# caja_universal.net
KiCad netlist of a schematic drawn in EAGLE
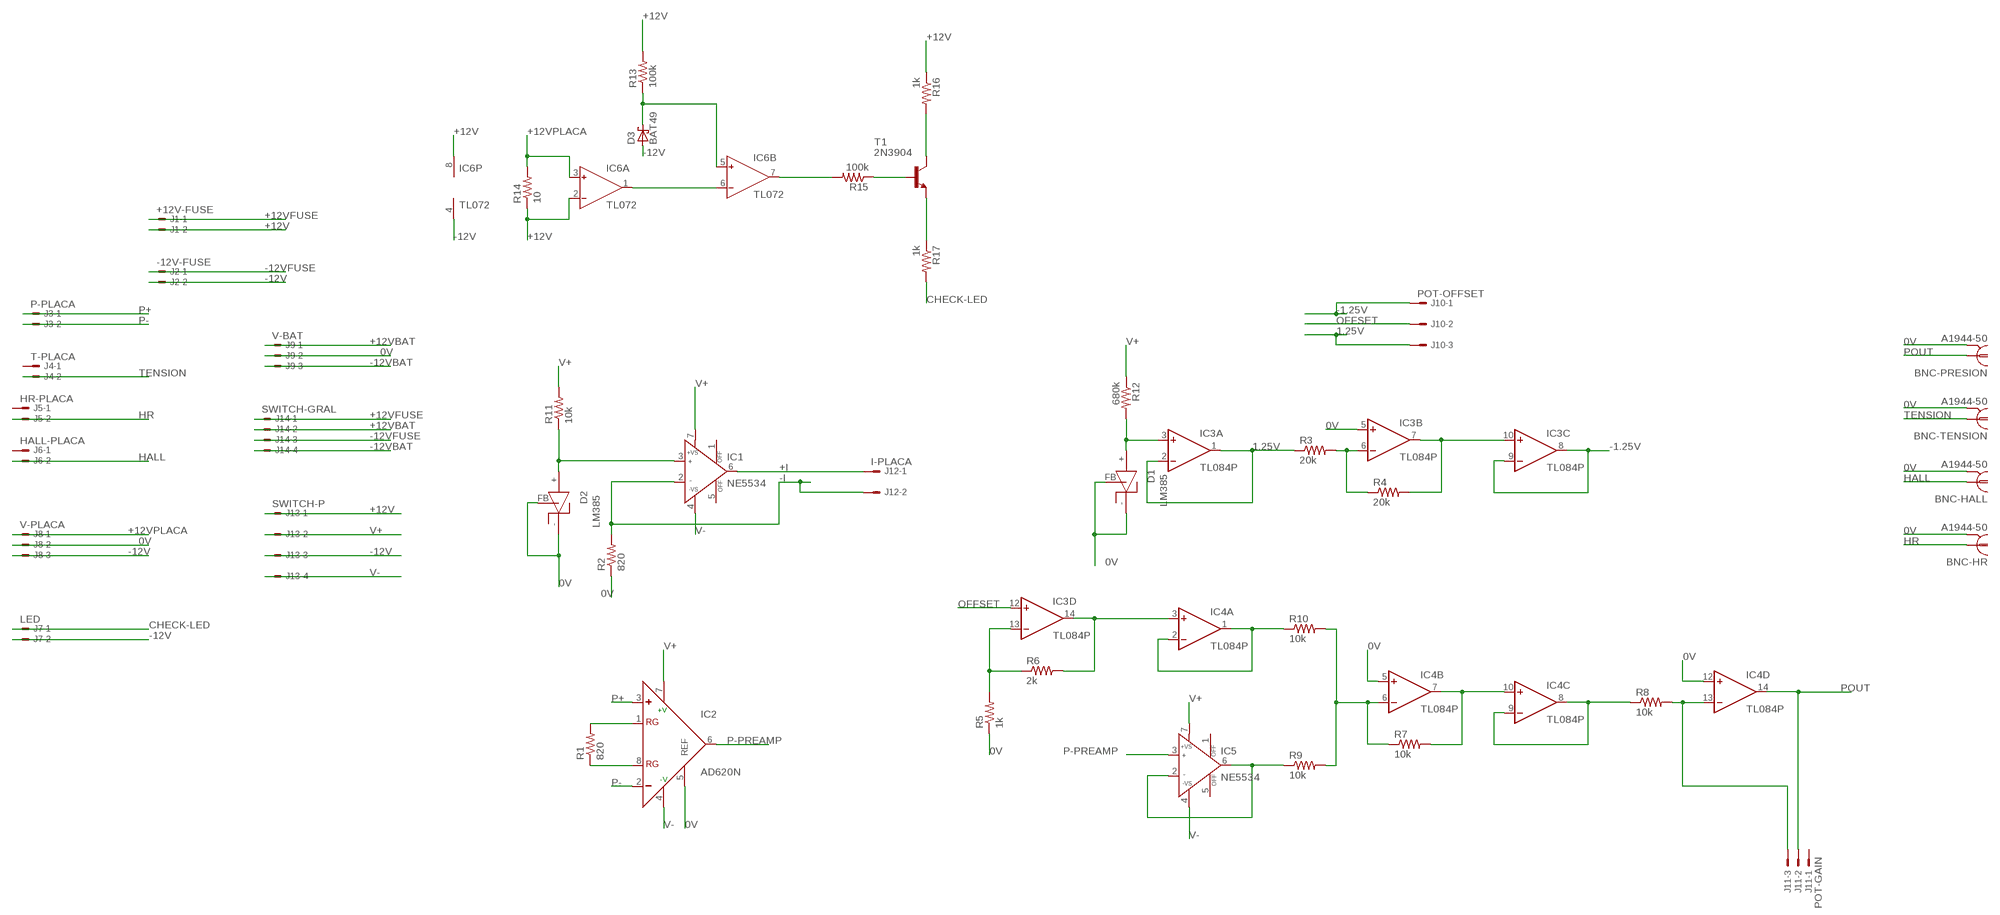
[diagram p0: schematic, sheet 1]

(export (version "E")
  (design (tool "Eeschema 10.0.6"))
  (components
    (comp (ref "BNC-HALL")
      (value "A1944-50")
      (footprint "eagle-import:A1944")
      (libsource (lib "eagle-import") (part "A1944-50"))
    )
    (comp (ref "BNC-HR")
      (value "A1944-50")
      (footprint "eagle-import:A1944")
      (libsource (lib "eagle-import") (part "A1944-50"))
    )
    (comp (ref "BNC-PRESION")
      (value "A1944-50")
      (footprint "eagle-import:A1944")
      (libsource (lib "eagle-import") (part "A1944-50"))
    )
    (comp (ref "BNC-TENSION")
      (value "A1944-50")
      (footprint "eagle-import:A1944")
      (libsource (lib "eagle-import") (part "A1944-50"))
    )
    (comp (ref "D1")
      (value "LM385")
      (footprint "eagle-import:TO-92")
      (libsource (lib "eagle-import") (part "LM385"))
    )
    (comp (ref "D2")
      (value "LM385")
      (footprint "eagle-import:TO-92")
      (libsource (lib "eagle-import") (part "LM385"))
    )
    (comp (ref "D3")
      (value "BAT49")
      (footprint "eagle-import:DO41-10")
      (libsource (lib "eagle-import") (part "BAT49"))
    )
    (comp (ref "IC1")
      (value "NE5534")
      (footprint "eagle-import:DIL08")
      (fields (field (name "MPN") "AD711BQ"))
      (libsource (lib "eagle-import") (part "AD711N"))
    )
    (comp (ref "IC2")
      (value "AD620N")
      (footprint "eagle-import:DIL08")
      (fields (field (name "MF") "ALTERA CORPORATION") (field (name "MPN") "AD620AN"))
      (libsource (lib "eagle-import") (part "AD620N"))
    )
    (comp (ref "IC3")
      (value "TL084P")
      (footprint "eagle-import:DIL14")
      (libsource (lib "eagle-import") (part "TL084P"))
    )
    (comp (ref "IC4")
      (value "TL084P")
      (footprint "eagle-import:DIL14")
      (libsource (lib "eagle-import") (part "TL084P"))
    )
    (comp (ref "IC5")
      (value "NE5534")
      (footprint "eagle-import:DIL08")
      (fields (field (name "MPN") "AD711BQ"))
      (libsource (lib "eagle-import") (part "AD711N"))
    )
    (comp (ref "IC6")
      (value "TL072")
      (footprint "eagle-import:DIL08")
      (fields (field (name "MF") "ALTERA CORPORATION") (field (name "MPN") "AD826ANZ"))
      (libsource (lib "eagle-import") (part "AD826N"))
    )
    (comp (ref "J1")
      (value "+12V-FUSE")
      (footprint "eagle-import:6410-02")
      (libsource (lib "eagle-import") (part "22-?-0227-2021"))
    )
    (comp (ref "J2")
      (value "-12V-FUSE")
      (footprint "eagle-import:6410-02")
      (libsource (lib "eagle-import") (part "22-?-0227-2021"))
    )
    (comp (ref "J3")
      (value "P-PLACA")
      (footprint "eagle-import:6410-02")
      (libsource (lib "eagle-import") (part "22-?-0227-2021"))
    )
    (comp (ref "J4")
      (value "T-PLACA")
      (footprint "eagle-import:6410-02")
      (libsource (lib "eagle-import") (part "22-?-0227-2021"))
    )
    (comp (ref "J5")
      (value "HR-PLACA")
      (footprint "eagle-import:6410-02")
      (libsource (lib "eagle-import") (part "22-?-0227-2021"))
    )
    (comp (ref "J6")
      (value "HALL-PLACA")
      (footprint "eagle-import:6410-02")
      (libsource (lib "eagle-import") (part "22-?-0227-2021"))
    )
    (comp (ref "J7")
      (value "LED")
      (footprint "eagle-import:6410-02")
      (libsource (lib "eagle-import") (part "22-?-0227-2021"))
    )
    (comp (ref "J8")
      (value "V-PLACA")
      (footprint "eagle-import:6410-03")
      (libsource (lib "eagle-import") (part "22-?-0327-2031"))
    )
    (comp (ref "J9")
      (value "V-BAT")
      (footprint "eagle-import:6410-03")
      (libsource (lib "eagle-import") (part "22-?-0327-2031"))
    )
    (comp (ref "J10")
      (value "POT-OFFSET")
      (footprint "eagle-import:6410-03")
      (libsource (lib "eagle-import") (part "22-?-0327-2031"))
    )
    (comp (ref "J11")
      (value "POT-GAIN")
      (footprint "eagle-import:6410-03")
      (libsource (lib "eagle-import") (part "22-?-0327-2031"))
    )
    (comp (ref "J12")
      (value "I-PLACA")
      (footprint "eagle-import:6410-02")
      (libsource (lib "eagle-import") (part "22-?-0227-2021"))
    )
    (comp (ref "J13")
      (value "SWITCH-P")
      (footprint "eagle-import:6410-04")
      (libsource (lib "eagle-import") (part "22-?-0427-2041"))
    )
    (comp (ref "J14")
      (value "SWITCH-GRAL")
      (footprint "eagle-import:6410-04")
      (libsource (lib "eagle-import") (part "22-?-0427-2041"))
    )
    (comp (ref "R1")
      (value "820")
      (footprint "eagle-import:0204_7")
      (libsource (lib "eagle-import") (part "R-US_0204/7"))
    )
    (comp (ref "R2")
      (value "820")
      (footprint "eagle-import:0204_7")
      (libsource (lib "eagle-import") (part "R-US_0204/7"))
    )
    (comp (ref "R3")
      (value "20k")
      (footprint "eagle-import:0204_7")
      (libsource (lib "eagle-import") (part "R-US_0204/7"))
    )
    (comp (ref "R4")
      (value "20k")
      (footprint "eagle-import:0204_7")
      (libsource (lib "eagle-import") (part "R-US_0204/7"))
    )
    (comp (ref "R5")
      (value "1k")
      (footprint "eagle-import:0204_7")
      (libsource (lib "eagle-import") (part "R-US_0204/7"))
    )
    (comp (ref "R6")
      (value "2k")
      (footprint "eagle-import:0204_7")
      (libsource (lib "eagle-import") (part "R-US_0204/7"))
    )
    (comp (ref "R7")
      (value "10k")
      (footprint "eagle-import:0204_7")
      (libsource (lib "eagle-import") (part "R-US_0204/7"))
    )
    (comp (ref "R8")
      (value "10k")
      (footprint "eagle-import:0204_7")
      (libsource (lib "eagle-import") (part "R-US_0204/7"))
    )
    (comp (ref "R9")
      (value "10k")
      (footprint "eagle-import:0204_7")
      (libsource (lib "eagle-import") (part "R-US_0204/7"))
    )
    (comp (ref "R10")
      (value "10k")
      (footprint "eagle-import:0204_7")
      (libsource (lib "eagle-import") (part "R-US_0204/7"))
    )
    (comp (ref "R11")
      (value "10k")
      (footprint "eagle-import:0204_7")
      (libsource (lib "eagle-import") (part "R-US_0204/7"))
    )
    (comp (ref "R12")
      (value "680k")
      (footprint "eagle-import:0204_7")
      (libsource (lib "eagle-import") (part "R-US_0204/7"))
    )
    (comp (ref "R13")
      (value "100k")
      (footprint "eagle-import:0204_7")
      (libsource (lib "eagle-import") (part "R-US_0204/7"))
    )
    (comp (ref "R14")
      (value "10")
      (footprint "eagle-import:0204_7")
      (libsource (lib "eagle-import") (part "R-US_0204/7"))
    )
    (comp (ref "R15")
      (value "100k")
      (footprint "eagle-import:0204_7")
      (libsource (lib "eagle-import") (part "R-US_0204/7"))
    )
    (comp (ref "R16")
      (value "1k")
      (footprint "eagle-import:0204_7")
      (libsource (lib "eagle-import") (part "R-US_0204/7"))
    )
    (comp (ref "R17")
      (value "1k")
      (footprint "eagle-import:0204_7")
      (libsource (lib "eagle-import") (part "R-US_0204/7"))
    )
    (comp (ref "T1")
      (value "2N3904")
      (footprint "eagle-import:TO92")
      (libsource (lib "eagle-import") (part "2N3904"))
    )
  )
  (nets
    (net (code "1") (name "/+12V") (class "Default")
      (node (ref "IC6") (pin "2") (pinfunction "IN-_2") (pintype "input"))
      (node (ref "IC6") (pin "8") (pinfunction "V+_8") (pintype "power_in"))
      (node (ref "J1") (pin "2") (pinfunction "S_2") (pintype "passive"))
      (node (ref "J13") (pin "1") (pinfunction "S_1") (pintype "passive"))
      (node (ref "R13") (pin "2") (pinfunction "2_2") (pintype "passive"))
      (node (ref "R14") (pin "1") (pinfunction "1_1") (pintype "passive"))
      (node (ref "R16") (pin "1") (pinfunction "1_1") (pintype "passive"))
    )
    (net (code "2") (name "/+12VBAT") (class "Default")
      (node (ref "J14") (pin "2") (pinfunction "S_2") (pintype "passive"))
      (node (ref "J9") (pin "1") (pinfunction "S_1") (pintype "passive"))
    )
    (net (code "3") (name "/+12VFUSE") (class "Default")
      (node (ref "J1") (pin "1") (pinfunction "S_1") (pintype "passive"))
      (node (ref "J14") (pin "1") (pinfunction "S_1") (pintype "passive"))
    )
    (net (code "4") (name "/+12VPLACA") (class "Default")
      (node (ref "IC6") (pin "3") (pinfunction "IN+_3") (pintype "input"))
      (node (ref "J8") (pin "1") (pinfunction "S_1") (pintype "passive"))
      (node (ref "R14") (pin "2") (pinfunction "2_2") (pintype "passive"))
    )
    (net (code "5") (name "/+I") (class "Default")
      (node (ref "IC1") (pin "6") (pinfunction "OUT_6") (pintype "output"))
      (node (ref "J12") (pin "1") (pinfunction "S_1") (pintype "passive"))
    )
    (net (code "6") (name "/-1.25V") (class "Default")
      (node (ref "IC3") (pin "8") (pinfunction "OUT_8") (pintype "output"))
      (node (ref "IC3") (pin "9") (pinfunction "-IN_9") (pintype "input"))
      (node (ref "J10") (pin "1") (pinfunction "S_1") (pintype "passive"))
    )
    (net (code "7") (name "/-12V") (class "Default")
      (node (ref "D3") (pin "A") (pinfunction "A_A") (pintype "passive"))
      (node (ref "IC6") (pin "4") (pinfunction "V-_4") (pintype "power_in"))
      (node (ref "J13") (pin "3") (pinfunction "S_3") (pintype "passive"))
      (node (ref "J2") (pin "2") (pinfunction "S_2") (pintype "passive"))
      (node (ref "J7") (pin "2") (pinfunction "S_2") (pintype "passive"))
      (node (ref "J8") (pin "3") (pinfunction "S_3") (pintype "passive"))
    )
    (net (code "8") (name "/-12VBAT") (class "Default")
      (node (ref "J14") (pin "4") (pinfunction "S_4") (pintype "passive"))
      (node (ref "J9") (pin "3") (pinfunction "S_3") (pintype "passive"))
    )
    (net (code "9") (name "/-12VFUSE") (class "Default")
      (node (ref "J14") (pin "3") (pinfunction "S_3") (pintype "passive"))
      (node (ref "J2") (pin "1") (pinfunction "S_1") (pintype "passive"))
    )
    (net (code "10") (name "/-I") (class "Default")
      (node (ref "IC1") (pin "2") (pinfunction "IN-_2") (pintype "input"))
      (node (ref "J12") (pin "2") (pinfunction "S_2") (pintype "passive"))
      (node (ref "R2") (pin "2") (pinfunction "2_2") (pintype "passive"))
    )
    (net (code "11") (name "/0V") (class "Default")
      (node (ref "BNC-HALL") (pin "2") (pinfunction "2_2") (pintype "passive"))
      (node (ref "BNC-HALL") (pin "3") (pinfunction "2_3") (pintype "passive"))
      (node (ref "BNC-HALL") (pin "4") (pinfunction "2_4") (pintype "passive"))
      (node (ref "BNC-HALL") (pin "5") (pinfunction "2_5") (pintype "passive"))
      (node (ref "BNC-HR") (pin "2") (pinfunction "2_2") (pintype "passive"))
      (node (ref "BNC-HR") (pin "3") (pinfunction "2_3") (pintype "passive"))
      (node (ref "BNC-HR") (pin "4") (pinfunction "2_4") (pintype "passive"))
      (node (ref "BNC-HR") (pin "5") (pinfunction "2_5") (pintype "passive"))
      (node (ref "BNC-PRESION") (pin "2") (pinfunction "2_2") (pintype "passive"))
      (node (ref "BNC-PRESION") (pin "3") (pinfunction "2_3") (pintype "passive"))
      (node (ref "BNC-PRESION") (pin "4") (pinfunction "2_4") (pintype "passive"))
      (node (ref "BNC-PRESION") (pin "5") (pinfunction "2_5") (pintype "passive"))
      (node (ref "BNC-TENSION") (pin "2") (pinfunction "2_2") (pintype "passive"))
      (node (ref "BNC-TENSION") (pin "3") (pinfunction "2_3") (pintype "passive"))
      (node (ref "BNC-TENSION") (pin "4") (pinfunction "2_4") (pintype "passive"))
      (node (ref "BNC-TENSION") (pin "5") (pinfunction "2_5") (pintype "passive"))
      (node (ref "D1") (pin "-") (pinfunction "-_-") (pintype "passive"))
      (node (ref "D1") (pin "FB") (pinfunction "FB_FB") (pintype "bidirectional"))
      (node (ref "D2") (pin "-") (pinfunction "-_-") (pintype "passive"))
      (node (ref "D2") (pin "FB") (pinfunction "FB_FB") (pintype "bidirectional"))
      (node (ref "IC2") (pin "5") (pinfunction "REF_5") (pintype "passive"))
      (node (ref "IC3") (pin "5") (pinfunction "+IN_5") (pintype "input"))
      (node (ref "IC4") (pin "12") (pinfunction "+IN_12") (pintype "input"))
      (node (ref "IC4") (pin "5") (pinfunction "+IN_5") (pintype "input"))
      (node (ref "J8") (pin "2") (pinfunction "S_2") (pintype "passive"))
      (node (ref "J9") (pin "2") (pinfunction "S_2") (pintype "passive"))
      (node (ref "R2") (pin "1") (pinfunction "1_1") (pintype "passive"))
      (node (ref "R5") (pin "1") (pinfunction "1_1") (pintype "passive"))
    )
    (net (code "12") (name "/1.25V") (class "Default")
      (node (ref "IC3") (pin "1") (pinfunction "OUT_1") (pintype "output"))
      (node (ref "IC3") (pin "2") (pinfunction "-IN_2") (pintype "input"))
      (node (ref "J10") (pin "3") (pinfunction "S_3") (pintype "passive"))
      (node (ref "R3") (pin "1") (pinfunction "1_1") (pintype "passive"))
    )
    (net (code "13") (name "/CHECK-LED") (class "Default")
      (node (ref "J7") (pin "1") (pinfunction "S_1") (pintype "passive"))
      (node (ref "R17") (pin "2") (pinfunction "2_2") (pintype "passive"))
    )
    (net (code "14") (name "/HALL") (class "Default")
      (node (ref "BNC-HALL") (pin "1") (pinfunction "1_1") (pintype "passive"))
      (node (ref "J6") (pin "2") (pinfunction "S_2") (pintype "passive"))
    )
    (net (code "15") (name "/HR") (class "Default")
      (node (ref "BNC-HR") (pin "1") (pinfunction "1_1") (pintype "passive"))
      (node (ref "J5") (pin "2") (pinfunction "S_2") (pintype "passive"))
    )
    (net (code "16") (name "/OFFSET") (class "Default")
      (node (ref "IC3") (pin "12") (pinfunction "+IN_12") (pintype "input"))
      (node (ref "J10") (pin "2") (pinfunction "S_2") (pintype "passive"))
    )
    (net (code "17") (name "/P+") (class "Default")
      (node (ref "IC2") (pin "3") (pinfunction "+_3") (pintype "input"))
      (node (ref "J3") (pin "1") (pinfunction "S_1") (pintype "passive"))
    )
    (net (code "18") (name "/P-") (class "Default")
      (node (ref "IC2") (pin "2") (pinfunction "-_2") (pintype "input"))
      (node (ref "J3") (pin "2") (pinfunction "S_2") (pintype "passive"))
    )
    (net (code "19") (name "/P-PREAMP") (class "Default")
      (node (ref "IC2") (pin "6") (pinfunction "OUT_6") (pintype "output"))
      (node (ref "IC5") (pin "3") (pinfunction "IN+_3") (pintype "input"))
    )
    (net (code "20") (name "/POUT") (class "Default")
      (node (ref "BNC-PRESION") (pin "1") (pinfunction "1_1") (pintype "passive"))
      (node (ref "IC4") (pin "14") (pinfunction "OUT_14") (pintype "output"))
      (node (ref "J11") (pin "2") (pinfunction "S_2") (pintype "passive"))
    )
    (net (code "21") (name "/TENSION") (class "Default")
      (node (ref "BNC-TENSION") (pin "1") (pinfunction "1_1") (pintype "passive"))
      (node (ref "J4") (pin "2") (pinfunction "S_2") (pintype "passive"))
    )
    (net (code "22") (name "/V+") (class "Default")
      (node (ref "IC1") (pin "7") (pinfunction "+VS_7") (pintype "input"))
      (node (ref "IC2") (pin "7") (pinfunction "+V_7") (pintype "power_in"))
      (node (ref "IC5") (pin "7") (pinfunction "+VS_7") (pintype "input"))
      (node (ref "J13") (pin "2") (pinfunction "S_2") (pintype "passive"))
      (node (ref "R11") (pin "2") (pinfunction "2_2") (pintype "passive"))
      (node (ref "R12") (pin "1") (pinfunction "1_1") (pintype "passive"))
    )
    (net (code "23") (name "/V-") (class "Default")
      (node (ref "IC1") (pin "4") (pinfunction "-VS_4") (pintype "input"))
      (node (ref "IC2") (pin "4") (pinfunction "-V_4") (pintype "power_in"))
      (node (ref "IC5") (pin "4") (pinfunction "-VS_4") (pintype "input"))
      (node (ref "J13") (pin "4") (pinfunction "S_4") (pintype "passive"))
    )
    (net (code "24") (name "Net-(IC1-IN+)") (class "Default")
      (node (ref "D2") (pin "+") (pinfunction "+_+") (pintype "passive"))
      (node (ref "IC1") (pin "3") (pinfunction "IN+_3") (pintype "input"))
      (node (ref "R11") (pin "1") (pinfunction "1_1") (pintype "passive"))
    )
    (net (code "25") (name "Net-(IC2-RG-Pad1)") (class "Default")
      (node (ref "IC2") (pin "1") (pinfunction "RG_1") (pintype "passive"))
      (node (ref "R1") (pin "2") (pinfunction "2_2") (pintype "passive"))
    )
    (net (code "26") (name "Net-(IC2-RG-Pad8)") (class "Default")
      (node (ref "IC2") (pin "8") (pinfunction "RG_8") (pintype "passive"))
      (node (ref "R1") (pin "1") (pinfunction "1_1") (pintype "passive"))
    )
    (net (code "27") (name "Net-(IC3A-+IN)") (class "Default")
      (node (ref "D1") (pin "+") (pinfunction "+_+") (pintype "passive"))
      (node (ref "IC3") (pin "3") (pinfunction "+IN_3") (pintype "input"))
      (node (ref "R12") (pin "2") (pinfunction "2_2") (pintype "passive"))
    )
    (net (code "28") (name "Net-(IC3B--IN)") (class "Default")
      (node (ref "IC3") (pin "6") (pinfunction "-IN_6") (pintype "input"))
      (node (ref "R3") (pin "2") (pinfunction "2_2") (pintype "passive"))
      (node (ref "R4") (pin "1") (pinfunction "1_1") (pintype "passive"))
    )
    (net (code "29") (name "Net-(IC3B-OUT)") (class "Default")
      (node (ref "IC3") (pin "10") (pinfunction "+IN_10") (pintype "input"))
      (node (ref "IC3") (pin "7") (pinfunction "OUT_7") (pintype "output"))
      (node (ref "R4") (pin "2") (pinfunction "2_2") (pintype "passive"))
    )
    (net (code "30") (name "Net-(IC3D--IN)") (class "Default")
      (node (ref "IC3") (pin "13") (pinfunction "-IN_13") (pintype "input"))
      (node (ref "R5") (pin "2") (pinfunction "2_2") (pintype "passive"))
      (node (ref "R6") (pin "1") (pinfunction "1_1") (pintype "passive"))
    )
    (net (code "31") (name "Net-(IC3D-OUT)") (class "Default")
      (node (ref "IC3") (pin "14") (pinfunction "OUT_14") (pintype "output"))
      (node (ref "IC4") (pin "3") (pinfunction "+IN_3") (pintype "input"))
      (node (ref "R6") (pin "2") (pinfunction "2_2") (pintype "passive"))
    )
    (net (code "32") (name "Net-(IC4A--IN)") (class "Default")
      (node (ref "IC4") (pin "1") (pinfunction "OUT_1") (pintype "output"))
      (node (ref "IC4") (pin "2") (pinfunction "-IN_2") (pintype "input"))
      (node (ref "R10") (pin "1") (pinfunction "1_1") (pintype "passive"))
    )
    (net (code "33") (name "Net-(IC4B--IN)") (class "Default")
      (node (ref "IC4") (pin "6") (pinfunction "-IN_6") (pintype "input"))
      (node (ref "R10") (pin "2") (pinfunction "2_2") (pintype "passive"))
      (node (ref "R7") (pin "1") (pinfunction "1_1") (pintype "passive"))
      (node (ref "R9") (pin "2") (pinfunction "2_2") (pintype "passive"))
    )
    (net (code "34") (name "Net-(IC4B-OUT)") (class "Default")
      (node (ref "IC4") (pin "10") (pinfunction "+IN_10") (pintype "input"))
      (node (ref "IC4") (pin "7") (pinfunction "OUT_7") (pintype "output"))
      (node (ref "R7") (pin "2") (pinfunction "2_2") (pintype "passive"))
    )
    (net (code "35") (name "Net-(IC4C--IN)") (class "Default")
      (node (ref "IC4") (pin "8") (pinfunction "OUT_8") (pintype "output"))
      (node (ref "IC4") (pin "9") (pinfunction "-IN_9") (pintype "input"))
      (node (ref "R8") (pin "1") (pinfunction "1_1") (pintype "passive"))
    )
    (net (code "36") (name "Net-(IC4D--IN)") (class "Default")
      (node (ref "IC4") (pin "13") (pinfunction "-IN_13") (pintype "input"))
      (node (ref "J11") (pin "3") (pinfunction "S_3") (pintype "passive"))
      (node (ref "R8") (pin "2") (pinfunction "2_2") (pintype "passive"))
    )
    (net (code "37") (name "Net-(IC5-IN-)") (class "Default")
      (node (ref "IC5") (pin "2") (pinfunction "IN-_2") (pintype "input"))
      (node (ref "IC5") (pin "6") (pinfunction "OUT_6") (pintype "output"))
      (node (ref "R9") (pin "1") (pinfunction "1_1") (pintype "passive"))
    )
    (net (code "38") (name "Net-(IC6A-OUT)") (class "Default")
      (node (ref "IC6") (pin "1") (pinfunction "OUT_1") (pintype "output"))
      (node (ref "IC6") (pin "6") (pinfunction "IN-_6") (pintype "input"))
    )
    (net (code "39") (name "Net-(IC6B-IN+)") (class "Default")
      (node (ref "D3") (pin "C") (pinfunction "C_C") (pintype "passive"))
      (node (ref "IC6") (pin "5") (pinfunction "IN+_5") (pintype "input"))
      (node (ref "R13") (pin "1") (pinfunction "1_1") (pintype "passive"))
    )
    (net (code "40") (name "Net-(IC6B-OUT)") (class "Default")
      (node (ref "IC6") (pin "7") (pinfunction "OUT_7") (pintype "output"))
      (node (ref "R15") (pin "2") (pinfunction "2_2") (pintype "passive"))
    )
    (net (code "41") (name "Net-(T1-B)") (class "Default")
      (node (ref "R15") (pin "1") (pinfunction "1_1") (pintype "passive"))
      (node (ref "T1") (pin "2") (pinfunction "B_2") (pintype "passive"))
    )
    (net (code "42") (name "Net-(T1-C)") (class "Default")
      (node (ref "R16") (pin "2") (pinfunction "2_2") (pintype "passive"))
      (node (ref "T1") (pin "1") (pinfunction "C_1") (pintype "passive"))
    )
    (net (code "43") (name "Net-(T1-E)") (class "Default")
      (node (ref "R17") (pin "1") (pinfunction "1_1") (pintype "passive"))
      (node (ref "T1") (pin "3") (pinfunction "E_3") (pintype "passive"))
    )
    (net (code "44") (name "unconnected-(IC1-OFF-Pad1)") (class "Default")
      (node (ref "IC1") (pin "1") (pinfunction "OFF_1") (pintype "passive"))
    )
    (net (code "45") (name "unconnected-(IC1-OFF-Pad5)") (class "Default")
      (node (ref "IC1") (pin "5") (pinfunction "OFF_5") (pintype "passive"))
    )
    (net (code "46") (name "unconnected-(IC5-OFF-Pad1)") (class "Default")
      (node (ref "IC5") (pin "1") (pinfunction "OFF_1") (pintype "passive"))
    )
    (net (code "47") (name "unconnected-(IC5-OFF-Pad5)") (class "Default")
      (node (ref "IC5") (pin "5") (pinfunction "OFF_5") (pintype "passive"))
    )
    (net (code "48") (name "unconnected-(J4A-S-Pad1)") (class "Default")
      (node (ref "J4") (pin "1") (pinfunction "S_1") (pintype "passive"))
    )
    (net (code "49") (name "unconnected-(J5A-S-Pad1)") (class "Default")
      (node (ref "J5") (pin "1") (pinfunction "S_1") (pintype "passive"))
    )
    (net (code "50") (name "unconnected-(J6A-S-Pad1)") (class "Default")
      (node (ref "J6") (pin "1") (pinfunction "S_1") (pintype "passive"))
    )
    (net (code "51") (name "unconnected-(J11A-S-Pad1)") (class "Default")
      (node (ref "J11") (pin "1") (pinfunction "S_1") (pintype "passive"))
    )
  )
)
